# Led_board.net
KiCad netlist of a schematic drawn in EAGLE
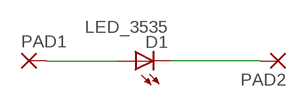
[diagram p0: schematic, sheet 1]

(export (version "E")
  (design (tool "Eeschema 10.0.6"))
  (components
    (comp (ref "D1")
      (value "LED_3535")
      (footprint "eagle-import:LED3535")
      (libsource (lib "eagle-import") (part "LED_3535"))
    )
    (comp (ref "PAD1")
      (value "2,15/1,0")
      (footprint "eagle-import:2,15_1,0")
      (libsource (lib "eagle-import") (part "2,15/1,0"))
    )
    (comp (ref "PAD2")
      (value "2,15/1,0")
      (footprint "eagle-import:2,15_1,0")
      (libsource (lib "eagle-import") (part "2,15/1,0"))
    )
  )
  (nets
    (net (code "1") (name "Net-(D1-A)") (class "Default")
      (node (ref "D1") (pin "P$1") (pinfunction "A_P$1") (pintype "passive"))
      (node (ref "PAD1") (pin "1") (pinfunction "P_1") (pintype "passive"))
    )
    (net (code "2") (name "Net-(D1-C)") (class "Default")
      (node (ref "D1") (pin "P$3") (pinfunction "C_P$3") (pintype "passive"))
      (node (ref "PAD2") (pin "1") (pinfunction "P_1") (pintype "passive"))
    )
  )
)
